# Main.net
KiCad netlist of a schematic drawn in EAGLE
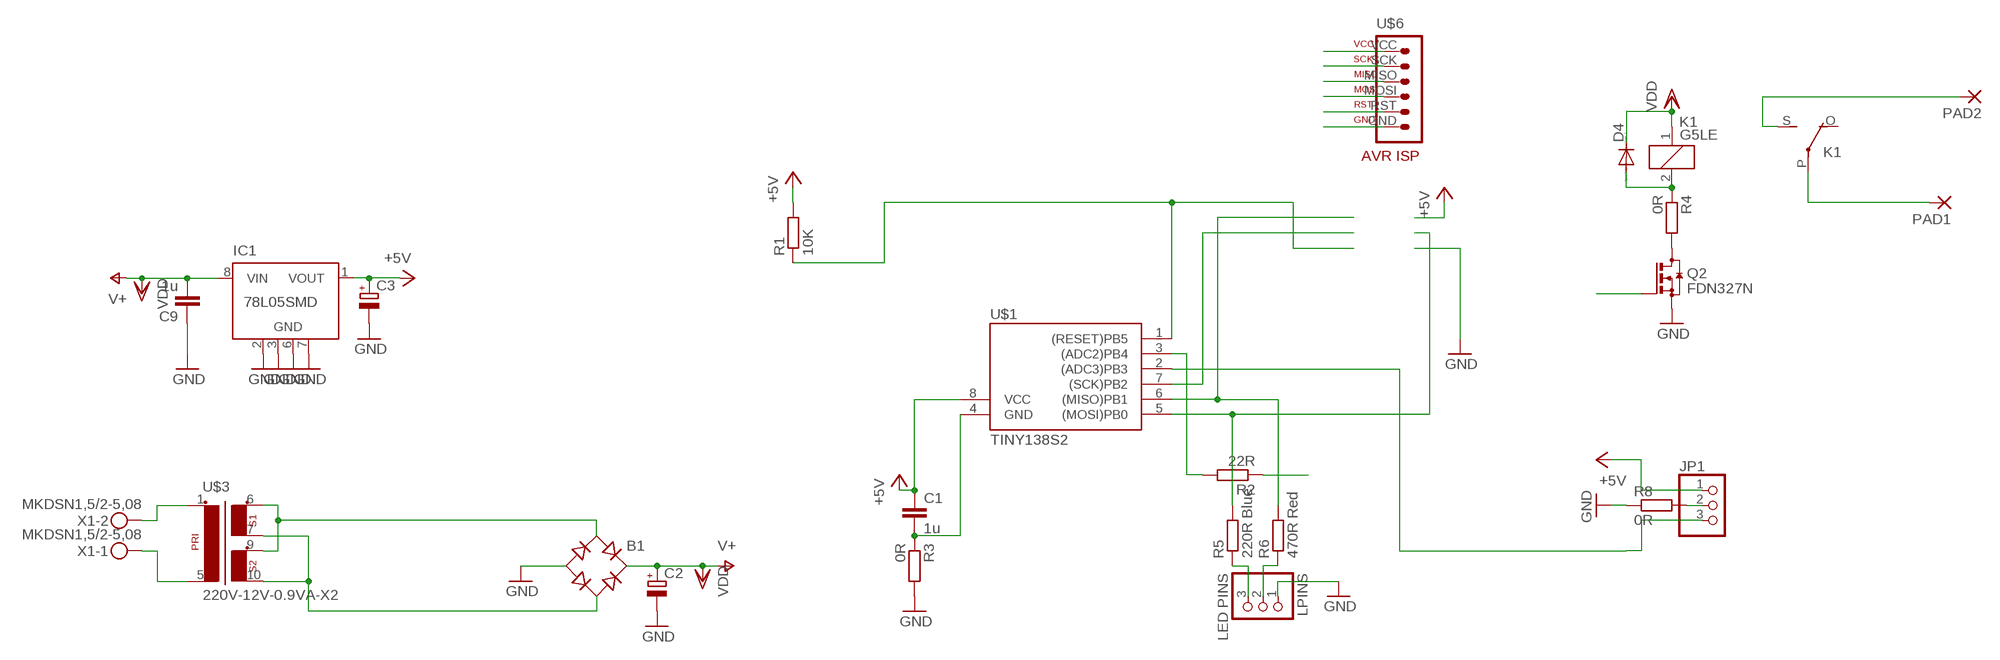
[diagram p0: schematic, sheet 1]
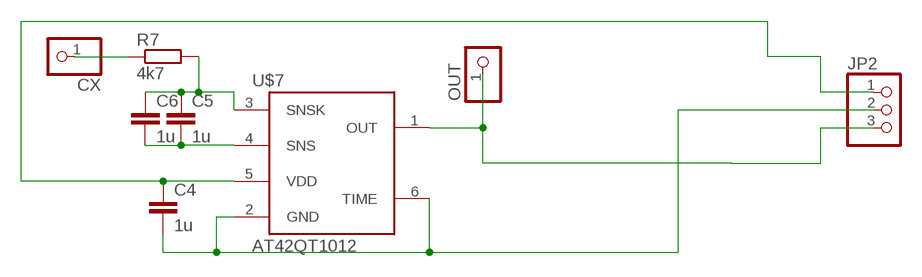
[diagram p1: schematic, sheet 2]

(export (version "E")
  (design (tool "Eeschema 10.0.6"))
  (components
    (comp (ref "B1")
      (value "RB1A")
      (footprint "eagle-import:RB1A")
      (libsource (lib "eagle-import") (part "RB1A"))
    )
    (comp (ref "C1")
      (value "1u")
      (footprint "eagle-import:C1206")
      (libsource (lib "eagle-import") (part "C-EUC1206"))
    )
    (comp (ref "C2")
      (value "CPOL-EUE5-13")
      (footprint "eagle-import:E5-13")
      (libsource (lib "eagle-import") (part "CPOL-EUE5-13"))
    )
    (comp (ref "C3")
      (value "CPOL-EUE2.5-7")
      (footprint "eagle-import:E2,5-7")
      (libsource (lib "eagle-import") (part "CPOL-EUE2.5-7"))
    )
    (comp (ref "C9")
      (value "1u")
      (footprint "eagle-import:C1206")
      (libsource (lib "eagle-import") (part "C-EUC1206"))
    )
    (comp (ref "D4")
      (value "DIODE-DO-214AC")
      (footprint "eagle-import:DO-214AC")
      (libsource (lib "eagle-import") (part "DIODE-DO-214AC"))
    )
    (comp (ref "IC1")
      (value "78L05SMD")
      (footprint "eagle-import:SO08")
      (libsource (lib "eagle-import") (part "78LSMD05"))
    )
    (comp (ref "JP1")
      (value "PINHD-1X3/90")
      (footprint "eagle-import:1X03_90")
      (libsource (lib "eagle-import") (part "PINHD-1X3/90"))
    )
    (comp (ref "K1")
      (value "G5LE")
      (footprint "eagle-import:G5LE")
      (libsource (lib "eagle-import") (part "G5LE"))
    )
    (comp (ref "LPINS")
      (value "LED PINS")
      (footprint "eagle-import:1X03")
      (libsource (lib "eagle-import") (part "PINHD-1X3"))
    )
    (comp (ref "PAD1")
      (value "3,81/1,4")
      (footprint "eagle-import:3,81_1,4")
      (libsource (lib "eagle-import") (part "3,81/1,4"))
    )
    (comp (ref "PAD2")
      (value "3,81/1,4")
      (footprint "eagle-import:3,81_1,4")
      (libsource (lib "eagle-import") (part "3,81/1,4"))
    )
    (comp (ref "Q2")
      (value "FDN327N")
      (footprint "eagle-import:SOT23")
      (libsource (lib "eagle-import") (part "BSS123"))
    )
    (comp (ref "R1")
      (value "10K")
      (footprint "eagle-import:R1206")
      (libsource (lib "eagle-import") (part "R-EU_R1206"))
    )
    (comp (ref "R2")
      (value "22R")
      (footprint "eagle-import:R1206")
      (libsource (lib "eagle-import") (part "R-EU_R1206"))
    )
    (comp (ref "R3")
      (value "0R")
      (footprint "eagle-import:R1206")
      (libsource (lib "eagle-import") (part "R-EU_R1206"))
    )
    (comp (ref "R4")
      (value "0R")
      (footprint "eagle-import:R1206")
      (libsource (lib "eagle-import") (part "R-EU_R1206"))
    )
    (comp (ref "R5")
      (value "220R Blue")
      (footprint "eagle-import:R1206")
      (libsource (lib "eagle-import") (part "R-EU_R1206"))
    )
    (comp (ref "R6")
      (value "470R Red")
      (footprint "eagle-import:R1206")
      (libsource (lib "eagle-import") (part "R-EU_R1206"))
    )
    (comp (ref "R8")
      (value "0R")
      (footprint "eagle-import:R1206")
      (libsource (lib "eagle-import") (part "R-EU_R1206"))
    )
    (comp (ref "U$1")
      (value "TINY138S2")
      (footprint "eagle-import:SO08")
      (libsource (lib "eagle-import") (part "TINY138S2"))
    )
    (comp (ref "U$3")
      (value "220V-12V-0.9VA-X2")
      (footprint "eagle-import:32.5-27.5-22")
      (libsource (lib "eagle-import") (part "220V-12V-0.9VA-X2"))
    )
    (comp (ref "U$6")
      (value "AVR-ISP-6-ROW")
      (footprint "eagle-import:AVR-ISP-6-ROW")
      (libsource (lib "eagle-import") (part "AVR-ISP-6-ROW"))
    )
    (comp (ref "X1")
      (value "MKDSN1,5/2-5,08")
      (footprint "eagle-import:MKDSN1,5_2-5,08")
      (libsource (lib "eagle-import") (part "MKDSN1,5/2-5,08"))
    )
    (comp (ref "C4")
      (value "1u")
      (footprint "eagle-import:C1206")
      (libsource (lib "eagle-import") (part "C-EUC1206"))
    )
    (comp (ref "C5")
      (value "1u")
      (footprint "eagle-import:C1206")
      (libsource (lib "eagle-import") (part "C-EUC1206"))
    )
    (comp (ref "C6")
      (value "1u")
      (footprint "eagle-import:C1206")
      (libsource (lib "eagle-import") (part "C-EUC1206"))
    )
    (comp (ref "CX")
      (value "PINHD-1X1")
      (footprint "eagle-import:1X01")
      (libsource (lib "eagle-import") (part "PINHD-1X1"))
    )
    (comp (ref "JP2")
      (value "PINHD-1X3/90")
      (footprint "eagle-import:1X03_90")
      (libsource (lib "eagle-import") (part "PINHD-1X3/90"))
    )
    (comp (ref "OUT")
      (value "PINHD-1X1")
      (footprint "eagle-import:1X01")
      (libsource (lib "eagle-import") (part "PINHD-1X1"))
    )
    (comp (ref "R7")
      (value "4k7")
      (footprint "eagle-import:R1206")
      (libsource (lib "eagle-import") (part "R-EU_R1206"))
    )
    (comp (ref "U$7")
      (value "AT42QT1012")
      (footprint "eagle-import:SOT23-6")
      (libsource (lib "eagle-import") (part "AT42QT1012"))
    )
  )
  (nets
    (net (code "1") (name "+5V") (class "Default")
      (node (ref "C1") (pin "1") (pinfunction "1_1") (pintype "passive"))
      (node (ref "C3") (pin "+") (pinfunction "+_+") (pintype "passive"))
      (node (ref "IC1") (pin "1") (pinfunction "VOUT_1") (pintype "output"))
      (node (ref "JP1") (pin "1") (pinfunction "1_1") (pintype "passive"))
      (node (ref "R1") (pin "2") (pinfunction "2_2") (pintype "passive"))
      (node (ref "U$1") (pin "8") (pinfunction "VCC_8") (pintype "power_in"))
      (node (ref "U$6") (pin "VCC") (pinfunction "VCC_VCC") (pintype "passive"))
    )
    (net (code "2") (name "GND") (class "Default")
      (node (ref "B1") (pin "-") (pinfunction "-_-") (pintype "passive"))
      (node (ref "C2") (pin "-") (pinfunction "-_-") (pintype "passive"))
      (node (ref "C3") (pin "-") (pinfunction "-_-") (pintype "passive"))
      (node (ref "C9") (pin "1") (pinfunction "1_1") (pintype "passive"))
      (node (ref "IC1") (pin "2") (pinfunction "GND_2") (pintype "power_in"))
      (node (ref "IC1") (pin "3") (pinfunction "GND_3") (pintype "power_in"))
      (node (ref "IC1") (pin "6") (pinfunction "GND_6") (pintype "power_in"))
      (node (ref "IC1") (pin "7") (pinfunction "GND_7") (pintype "power_in"))
      (node (ref "LPINS") (pin "1") (pinfunction "1_1") (pintype "passive"))
      (node (ref "Q2") (pin "2") (pinfunction "S_2") (pintype "passive"))
      (node (ref "R3") (pin "2") (pinfunction "2_2") (pintype "passive"))
      (node (ref "R8") (pin "1") (pinfunction "1_1") (pintype "passive"))
      (node (ref "U$6") (pin "GND") (pinfunction "GND_GND") (pintype "passive"))
    )
    (net (code "3") (name "N$1") (class "Default")
      (node (ref "R1") (pin "1") (pinfunction "1_1") (pintype "passive"))
      (node (ref "U$1") (pin "1") (pinfunction "(RESET)PB5_1") (pintype "bidirectional"))
      (node (ref "U$6") (pin "RST") (pinfunction "RST_RST") (pintype "passive"))
    )
    (net (code "4") (name "N$3") (class "Default")
      (node (ref "U$1") (pin "7") (pinfunction "(SCK)PB2_7") (pintype "bidirectional"))
      (node (ref "U$6") (pin "SCK") (pinfunction "SCK_SCK") (pintype "passive"))
    )
    (net (code "5") (name "N$4") (class "Default")
      (node (ref "R6") (pin "2") (pinfunction "2_2") (pintype "passive"))
      (node (ref "U$1") (pin "6") (pinfunction "(MISO)PB1_6") (pintype "bidirectional"))
      (node (ref "U$6") (pin "MISO") (pinfunction "MISO_MISO") (pintype "passive"))
    )
    (net (code "6") (name "N$5") (class "Default")
      (node (ref "R5") (pin "2") (pinfunction "2_2") (pintype "passive"))
      (node (ref "U$1") (pin "5") (pinfunction "(MOSI)PB0_5") (pintype "bidirectional"))
      (node (ref "U$6") (pin "MOSI") (pinfunction "MOSI_MOSI") (pintype "passive"))
    )
    (net (code "7") (name "N$9") (class "Default")
      (node (ref "Q2") (pin "1") (pinfunction "G_1") (pintype "passive"))
      (node (ref "R2") (pin "1") (pinfunction "1_1") (pintype "passive"))
    )
    (net (code "8") (name "Net-(CX-Pad1)") (class "Default")
      (node (ref "CX") (pin "1") (pinfunction "1_1") (pintype "passive"))
      (node (ref "R7") (pin "1") (pinfunction "1_1") (pintype "passive"))
    )
    (net (code "9") (name "Net-(D4-PadA)") (class "Default")
      (node (ref "D4") (pin "A") (pinfunction "A_A") (pintype "passive"))
      (node (ref "K1") (pin "2") (pinfunction "2_2") (pintype "passive"))
      (node (ref "R4") (pin "1") (pinfunction "1_1") (pintype "passive"))
    )
    (net (code "10") (name "Net-(JP1-Pad2)") (class "Default")
      (node (ref "JP1") (pin "2") (pinfunction "2_2") (pintype "passive"))
      (node (ref "R8") (pin "2") (pinfunction "2_2") (pintype "passive"))
    )
    (net (code "11") (name "Net-(LPINS-Pad2)") (class "Default")
      (node (ref "LPINS") (pin "2") (pinfunction "2_2") (pintype "passive"))
      (node (ref "R6") (pin "1") (pinfunction "1_1") (pintype "passive"))
    )
    (net (code "12") (name "Net-(LPINS-Pad3)") (class "Default")
      (node (ref "LPINS") (pin "3") (pinfunction "3_3") (pintype "passive"))
      (node (ref "R5") (pin "1") (pinfunction "1_1") (pintype "passive"))
    )
    (net (code "13") (name "Net-(PAD1-P)") (class "Default")
      (node (ref "K1") (pin "P") (pinfunction "P_P") (pintype "passive"))
      (node (ref "PAD1") (pin "1") (pinfunction "P_1") (pintype "passive"))
    )
    (net (code "14") (name "Net-(PAD2-P)") (class "Default")
      (node (ref "K1") (pin "S") (pinfunction "S_S") (pintype "passive"))
      (node (ref "PAD2") (pin "1") (pinfunction "P_1") (pintype "passive"))
    )
    (net (code "15") (name "Net-(Q2-D)") (class "Default")
      (node (ref "Q2") (pin "3") (pinfunction "D_3") (pintype "passive"))
      (node (ref "R4") (pin "2") (pinfunction "2_2") (pintype "passive"))
    )
    (net (code "16") (name "Net-(U$1-(ADC2)PB4)") (class "Default")
      (node (ref "R2") (pin "2") (pinfunction "2_2") (pintype "passive"))
      (node (ref "U$1") (pin "3") (pinfunction "(ADC2)PB4_3") (pintype "bidirectional"))
    )
    (net (code "17") (name "Net-(U$1-(ADC3)PB3)") (class "Default")
      (node (ref "JP1") (pin "3") (pinfunction "3_3") (pintype "passive"))
      (node (ref "U$1") (pin "2") (pinfunction "(ADC3)PB3_2") (pintype "bidirectional"))
    )
    (net (code "18") (name "Net-(U$1-GND)") (class "Default")
      (node (ref "C1") (pin "2") (pinfunction "2_2") (pintype "passive"))
      (node (ref "R3") (pin "1") (pinfunction "1_1") (pintype "passive"))
      (node (ref "U$1") (pin "4") (pinfunction "GND_4") (pintype "power_in"))
    )
    (net (code "19") (name "Net-(U$3-P1-1)") (class "Default")
      (node (ref "U$3") (pin "1") (pinfunction "P1-1_1") (pintype "passive"))
      (node (ref "X1") (pin "2") (pinfunction "KL_2") (pintype "passive"))
    )
    (net (code "20") (name "Net-(U$3-P1-2)") (class "Default")
      (node (ref "U$3") (pin "5") (pinfunction "P1-2_5") (pintype "passive"))
      (node (ref "X1") (pin "1") (pinfunction "KL_1") (pintype "passive"))
    )
    (net (code "21") (name "Net-(U$3-S1-1)") (class "Default")
      (node (ref "B1") (pin "AC1") (pinfunction "AC1_AC1") (pintype "passive"))
      (node (ref "U$3") (pin "6") (pinfunction "S1-1_6") (pintype "passive"))
      (node (ref "U$3") (pin "9") (pinfunction "S2-1_9") (pintype "passive"))
    )
    (net (code "22") (name "Net-(U$3-S1-2)") (class "Default")
      (node (ref "B1") (pin "AC2") (pinfunction "AC2_AC2") (pintype "passive"))
      (node (ref "U$3") (pin "10") (pinfunction "S2-2_10") (pintype "passive"))
      (node (ref "U$3") (pin "7") (pinfunction "S1-2_7") (pintype "passive"))
    )
    (net (code "23") (name "Net-(U$7-GND)") (class "Default")
      (node (ref "C4") (pin "2") (pinfunction "2_2") (pintype "passive"))
      (node (ref "JP2") (pin "2") (pinfunction "2_2") (pintype "passive"))
      (node (ref "U$7") (pin "2") (pinfunction "GND_2") (pintype "bidirectional"))
      (node (ref "U$7") (pin "6") (pinfunction "TIME_6") (pintype "bidirectional"))
    )
    (net (code "24") (name "Net-(U$7-OUT)") (class "Default")
      (node (ref "JP2") (pin "3") (pinfunction "3_3") (pintype "passive"))
      (node (ref "OUT") (pin "1") (pinfunction "1_1") (pintype "passive"))
      (node (ref "U$7") (pin "1") (pinfunction "OUT_1") (pintype "bidirectional"))
    )
    (net (code "25") (name "Net-(U$7-SNS)") (class "Default")
      (node (ref "C5") (pin "2") (pinfunction "2_2") (pintype "passive"))
      (node (ref "C6") (pin "2") (pinfunction "2_2") (pintype "passive"))
      (node (ref "U$7") (pin "4") (pinfunction "SNS_4") (pintype "bidirectional"))
    )
    (net (code "26") (name "Net-(U$7-SNSK)") (class "Default")
      (node (ref "C5") (pin "1") (pinfunction "1_1") (pintype "passive"))
      (node (ref "C6") (pin "1") (pinfunction "1_1") (pintype "passive"))
      (node (ref "R7") (pin "2") (pinfunction "2_2") (pintype "passive"))
      (node (ref "U$7") (pin "3") (pinfunction "SNSK_3") (pintype "bidirectional"))
    )
    (net (code "27") (name "Net-(U$7-VDD)") (class "Default")
      (node (ref "C4") (pin "1") (pinfunction "1_1") (pintype "passive"))
      (node (ref "JP2") (pin "1") (pinfunction "1_1") (pintype "passive"))
      (node (ref "U$7") (pin "5") (pinfunction "VDD_5") (pintype "bidirectional"))
    )
    (net (code "28") (name "V+") (class "Default")
      (node (ref "B1") (pin "+") (pinfunction "+_+") (pintype "passive"))
      (node (ref "C2") (pin "+") (pinfunction "+_+") (pintype "passive"))
      (node (ref "C9") (pin "2") (pinfunction "2_2") (pintype "passive"))
      (node (ref "D4") (pin "C") (pinfunction "C_C") (pintype "passive"))
      (node (ref "IC1") (pin "8") (pinfunction "VIN_8") (pintype "passive"))
      (node (ref "K1") (pin "1") (pinfunction "1_1") (pintype "passive"))
    )
    (net (code "29") (name "unconnected-(K1-PadO)") (class "Default")
      (node (ref "K1") (pin "O") (pinfunction "O_O") (pintype "passive"))
    )
  )
)
